# PowerManagementMysensors.net
KiCad netlist of a schematic drawn in EAGLE
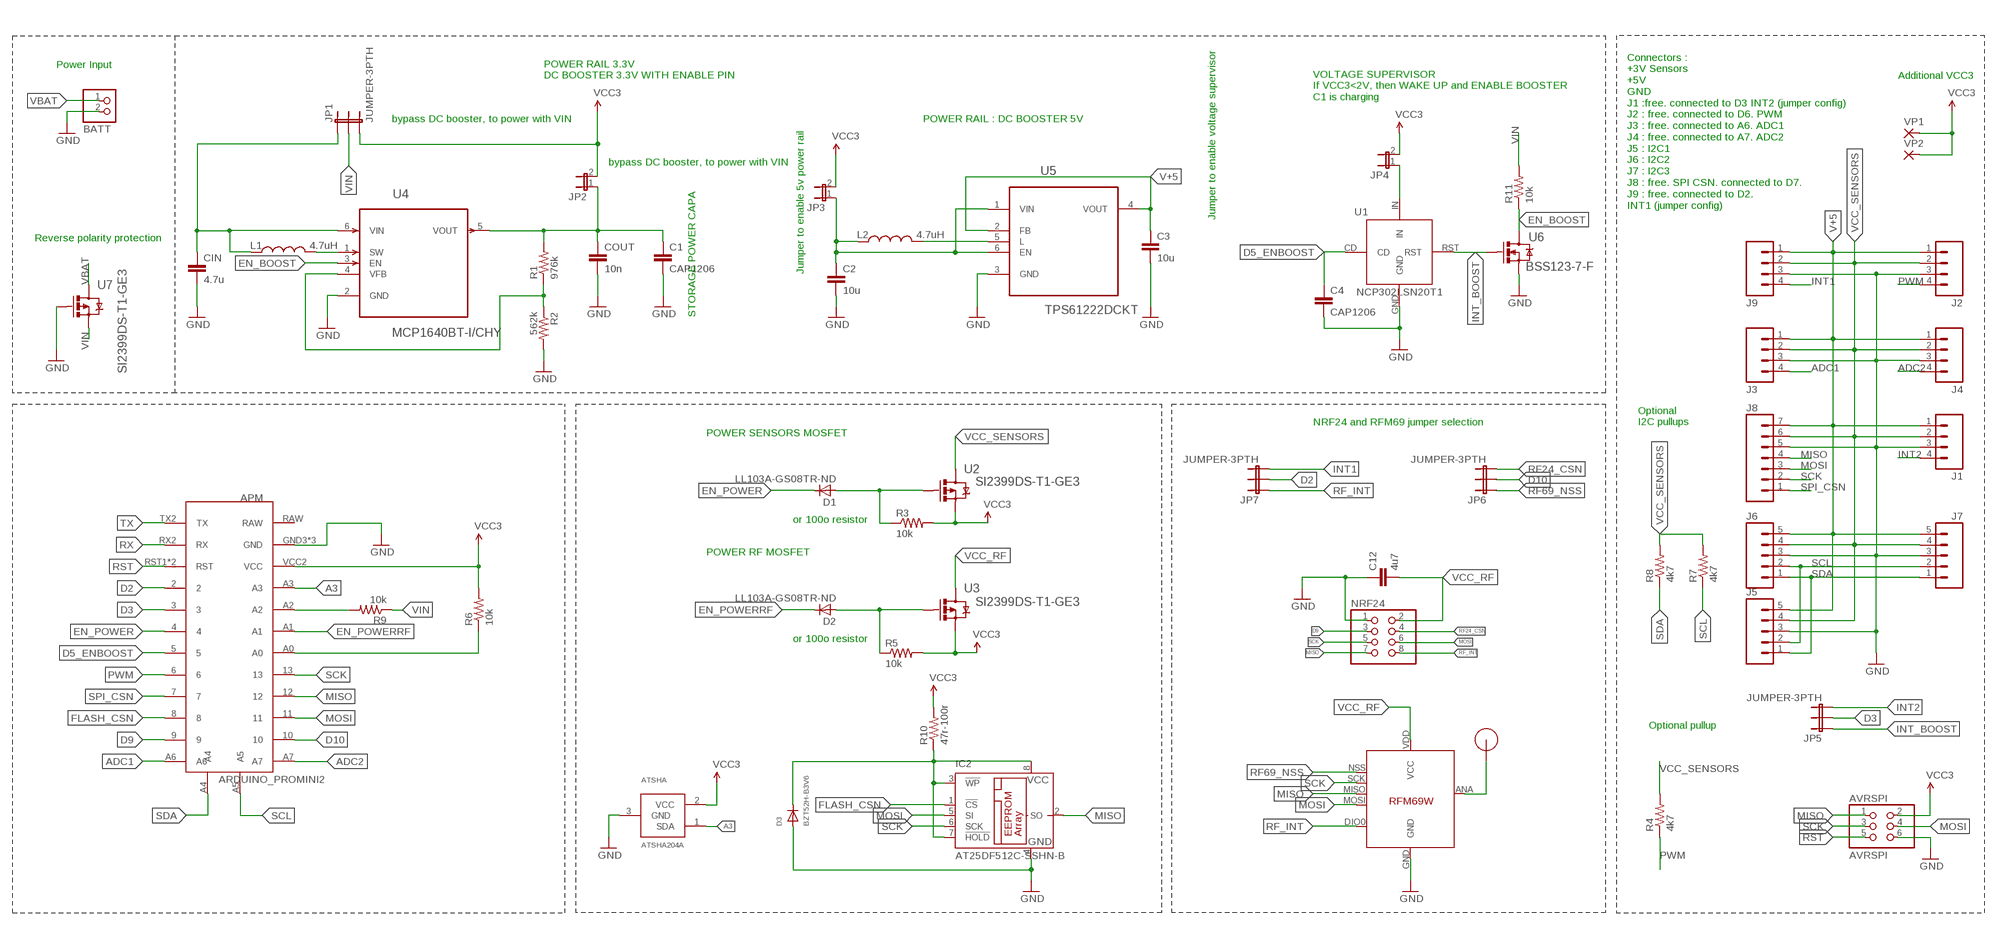
[diagram p0: schematic, sheet 1]

(export (version "E")
  (design (tool "Eeschema 10.0.6"))
  (components
    (comp (ref "ANT")
      (value "RFM12B_ANTENNA")
      (footprint "eagle-import:RFM12B-ANTENNA")
      (libsource (lib "eagle-import") (part "RFM12B_ANTENNA"))
    )
    (comp (ref "APM")
      (value "ARDUINO_PROMINI2")
      (footprint "eagle-import:ARDUINO_PROMINI2")
      (libsource (lib "eagle-import") (part "ARDUINO_PROMINI2"))
    )
    (comp (ref "ATSHA")
      (value "ATSHA204A")
      (footprint "eagle-import:SOT23")
      (libsource (lib "eagle-import") (part "ATSHA204A"))
    )
    (comp (ref "AVRSPI")
      (value "AVRSPI")
      (footprint "eagle-import:2X03")
      (libsource (lib "eagle-import") (part "PINHD-2X3"))
    )
    (comp (ref "BATT")
      (value "JST_2PIN-THM")
      (footprint "eagle-import:JST-PH-2-THM")
      (libsource (lib "eagle-import") (part "JST_2PIN-THM"))
    )
    (comp (ref "C1")
      (value "CAP1206")
      (footprint "eagle-import:CAP1206")
      (libsource (lib "eagle-import") (part "CAP1206"))
    )
    (comp (ref "C2")
      (value "10u")
      (footprint "eagle-import:CAP1206")
      (libsource (lib "eagle-import") (part "CAP1206"))
    )
    (comp (ref "C3")
      (value "10u")
      (footprint "eagle-import:CAP1206")
      (libsource (lib "eagle-import") (part "CAP1206"))
    )
    (comp (ref "C4")
      (value "CAP1206")
      (footprint "eagle-import:CAP1206")
      (libsource (lib "eagle-import") (part "CAP1206"))
    )
    (comp (ref "C12")
      (value "4u7")
      (footprint "eagle-import:CAP1206")
      (libsource (lib "eagle-import") (part "CAP1206"))
    )
    (comp (ref "CIN")
      (value "4.7u")
      (footprint "eagle-import:CAP1206")
      (libsource (lib "eagle-import") (part "CAP1206"))
    )
    (comp (ref "COUT")
      (value "10n")
      (footprint "eagle-import:CAP1206")
      (libsource (lib "eagle-import") (part "CAP1206"))
    )
    (comp (ref "D1")
      (value "LL103A-GS08TR-ND")
      (footprint "eagle-import:SOD80")
      (libsource (lib "eagle-import") (part "D-SOD-80"))
    )
    (comp (ref "D2")
      (value "LL103A-GS08TR-ND")
      (footprint "eagle-import:SOD80")
      (libsource (lib "eagle-import") (part "D-SOD-80"))
    )
    (comp (ref "D3")
      (value "BZT52H-B3V6")
      (footprint "eagle-import:SOD-123")
      (libsource (lib "eagle-import") (part "DIODESOD-123"))
    )
    (comp (ref "IC2")
      (value "AT25DF512C-SSHN-B")
      (footprint "eagle-import:SO-08")
      (fields (field (name "MF") "MICROCHIP") (field (name "MPN") "25AA080/SN"))
      (libsource (lib "eagle-import") (part "25SNAA080"))
    )
    (comp (ref "J1")
      (value "M041X04_NO_SILK")
      (footprint "eagle-import:1X04_NO_SILK")
      (libsource (lib "eagle-import") (part "M041X04_NO_SILK"))
    )
    (comp (ref "J2")
      (value "M041X04_NO_SILK")
      (footprint "eagle-import:1X04_NO_SILK")
      (libsource (lib "eagle-import") (part "M041X04_NO_SILK"))
    )
    (comp (ref "J3")
      (value "M041X04_NO_SILK")
      (footprint "eagle-import:1X04_NO_SILK")
      (libsource (lib "eagle-import") (part "M041X04_NO_SILK"))
    )
    (comp (ref "J4")
      (value "M041X04_NO_SILK")
      (footprint "eagle-import:1X04_NO_SILK")
      (libsource (lib "eagle-import") (part "M041X04_NO_SILK"))
    )
    (comp (ref "J5")
      (value "M05NO_SILK")
      (footprint "eagle-import:1X05_NO_SILK")
      (libsource (lib "eagle-import") (part "M05NO_SILK"))
    )
    (comp (ref "J6")
      (value "M05NO_SILK")
      (footprint "eagle-import:1X05_NO_SILK")
      (libsource (lib "eagle-import") (part "M05NO_SILK"))
    )
    (comp (ref "J7")
      (value "M05NO_SILK")
      (footprint "eagle-import:1X05_NO_SILK")
      (libsource (lib "eagle-import") (part "M05NO_SILK"))
    )
    (comp (ref "J8")
      (value "M07")
      (footprint "eagle-import:1X07")
      (libsource (lib "eagle-import") (part "M07"))
    )
    (comp (ref "J9")
      (value "M041X04_NO_SILK")
      (footprint "eagle-import:1X04_NO_SILK")
      (libsource (lib "eagle-import") (part "M041X04_NO_SILK"))
    )
    (comp (ref "JP1")
      (value "JUMPER-3PTH")
      (footprint "eagle-import:1X03")
      (libsource (lib "eagle-import") (part "JUMPER-3PTH"))
    )
    (comp (ref "JP2")
      (value "JUMPER-2PTH")
      (footprint "eagle-import:1X02")
      (libsource (lib "eagle-import") (part "JUMPER-2PTH"))
    )
    (comp (ref "JP3")
      (value "JUMPER-2PTH")
      (footprint "eagle-import:1X02")
      (libsource (lib "eagle-import") (part "JUMPER-2PTH"))
    )
    (comp (ref "JP4")
      (value "JUMPER-2PTH")
      (footprint "eagle-import:1X02")
      (libsource (lib "eagle-import") (part "JUMPER-2PTH"))
    )
    (comp (ref "JP5")
      (value "JUMPER-3PTH")
      (footprint "eagle-import:1X03")
      (libsource (lib "eagle-import") (part "JUMPER-3PTH"))
    )
    (comp (ref "JP6")
      (value "JUMPER-3PTH")
      (footprint "eagle-import:1X03")
      (libsource (lib "eagle-import") (part "JUMPER-3PTH"))
    )
    (comp (ref "JP7")
      (value "JUMPER-3PTH")
      (footprint "eagle-import:1X03")
      (libsource (lib "eagle-import") (part "JUMPER-3PTH"))
    )
    (comp (ref "L1")
      (value "4.7uH")
      (footprint "eagle-import:0805")
      (libsource (lib "eagle-import") (part "INDUCTOR0805"))
    )
    (comp (ref "L2")
      (value "4.7uH")
      (footprint "eagle-import:0805")
      (libsource (lib "eagle-import") (part "INDUCTOR0805"))
    )
    (comp (ref "NRF24")
      (value "PINHD-2X4")
      (footprint "eagle-import:2X04")
      (libsource (lib "eagle-import") (part "PINHD-2X4"))
    )
    (comp (ref "R1")
      (value "976k")
      (footprint "eagle-import:1206")
      (libsource (lib "eagle-import") (part "RESISTOR1206"))
    )
    (comp (ref "R2")
      (value "562k")
      (footprint "eagle-import:1206")
      (libsource (lib "eagle-import") (part "RESISTOR1206"))
    )
    (comp (ref "R3")
      (value "10k")
      (footprint "eagle-import:1206")
      (libsource (lib "eagle-import") (part "RESISTOR1206"))
    )
    (comp (ref "R4")
      (value "4k7")
      (footprint "eagle-import:1206")
      (libsource (lib "eagle-import") (part "RESISTOR1206"))
    )
    (comp (ref "R5")
      (value "10k")
      (footprint "eagle-import:1206")
      (libsource (lib "eagle-import") (part "RESISTOR1206"))
    )
    (comp (ref "R6")
      (value "10k")
      (footprint "eagle-import:1206")
      (libsource (lib "eagle-import") (part "RESISTOR1206"))
    )
    (comp (ref "R7")
      (value "4k7")
      (footprint "eagle-import:1206")
      (libsource (lib "eagle-import") (part "RESISTOR1206"))
    )
    (comp (ref "R8")
      (value "4k7")
      (footprint "eagle-import:1206")
      (libsource (lib "eagle-import") (part "RESISTOR1206"))
    )
    (comp (ref "R9")
      (value "10k")
      (footprint "eagle-import:1206")
      (libsource (lib "eagle-import") (part "RESISTOR1206"))
    )
    (comp (ref "R10")
      (value "47r-100r")
      (footprint "eagle-import:1206")
      (libsource (lib "eagle-import") (part "RESISTOR1206"))
    )
    (comp (ref "R11")
      (value "10k")
      (footprint "eagle-import:1206")
      (libsource (lib "eagle-import") (part "RESISTOR1206"))
    )
    (comp (ref "RFM69")
      (value "RFM69")
      (footprint "eagle-import:RFM69W-MINPADS")
      (libsource (lib "eagle-import") (part "RFM69"))
    )
    (comp (ref "U1")
      (value "NCP302LSN20T1")
      (footprint "eagle-import:NCP302LSN20T1")
      (libsource (lib "eagle-import") (part "NCP302LSN20T1"))
    )
    (comp (ref "U2")
      (value "SI2399DS-T1-GE3")
      (footprint "eagle-import:SOT95P237X112-3N")
      (libsource (lib "eagle-import") (part "SI2399DS-T1-GE3"))
    )
    (comp (ref "U3")
      (value "SI2399DS-T1-GE3")
      (footprint "eagle-import:SOT95P237X112-3N")
      (libsource (lib "eagle-import") (part "SI2399DS-T1-GE3"))
    )
    (comp (ref "U4")
      (value "MCP1640BT-I/CHY")
      (footprint "eagle-import:SOT95P270X145-6N")
      (libsource (lib "eagle-import") (part "MCP1640BT-I/CHY"))
    )
    (comp (ref "U5")
      (value "TPS61222DCKT")
      (footprint "eagle-import:SOT65P210X110-6N")
      (libsource (lib "eagle-import") (part "TPS61222DCKT"))
    )
    (comp (ref "U6")
      (value "BSS123-7-F")
      (footprint "eagle-import:SOT95P240X110-3N")
      (libsource (lib "eagle-import") (part "BSS123-7-F"))
    )
    (comp (ref "U7")
      (value "SI2399DS-T1-GE3")
      (footprint "eagle-import:SOT95P237X112-3N")
      (libsource (lib "eagle-import") (part "SI2399DS-T1-GE3"))
    )
    (comp (ref "VP1")
      (value "1,6/0,9")
      (footprint "eagle-import:1,6_0,9")
      (libsource (lib "eagle-import") (part "1,6/0,9"))
    )
    (comp (ref "VP2")
      (value "1,6/0,9")
      (footprint "eagle-import:1,6_0,9")
      (libsource (lib "eagle-import") (part "1,6/0,9"))
    )
  )
  (nets
    (net (code "1") (name "A3") (class "Default")
      (node (ref "APM") (pin "A3") (pinfunction "A3_A3") (pintype "bidirectional"))
      (node (ref "ATSHA") (pin "1") (pinfunction "SDA_1") (pintype "bidirectional"))
    )
    (net (code "2") (name "ADC1") (class "Default")
      (node (ref "APM") (pin "A6") (pinfunction "A6_A6") (pintype "bidirectional"))
      (node (ref "J3") (pin "4") (pinfunction "4_4") (pintype "passive"))
    )
    (net (code "3") (name "ADC2") (class "Default")
      (node (ref "APM") (pin "A7") (pinfunction "A7_A7") (pintype "bidirectional"))
      (node (ref "J4") (pin "4") (pinfunction "4_4") (pintype "passive"))
    )
    (net (code "4") (name "D2") (class "Default")
      (node (ref "APM") (pin "2") (pinfunction "2_2") (pintype "bidirectional"))
      (node (ref "JP7") (pin "2") (pinfunction "2_2") (pintype "passive"))
    )
    (net (code "5") (name "D3") (class "Default")
      (node (ref "APM") (pin "3") (pinfunction "3_3") (pintype "bidirectional"))
      (node (ref "JP5") (pin "2") (pinfunction "2_2") (pintype "passive"))
    )
    (net (code "6") (name "D5_ENBOOST") (class "Default")
      (node (ref "APM") (pin "5") (pinfunction "5_5") (pintype "bidirectional"))
      (node (ref "C4") (pin "1") (pinfunction "1_1") (pintype "passive"))
      (node (ref "U1") (pin "CD") (pinfunction "CD_CD") (pintype "bidirectional"))
    )
    (net (code "7") (name "D9") (class "Default")
      (node (ref "APM") (pin "9") (pinfunction "9_9") (pintype "bidirectional"))
      (node (ref "NRF24") (pin "3") (pinfunction "3_3") (pintype "passive"))
    )
    (net (code "8") (name "D10") (class "Default")
      (node (ref "APM") (pin "10") (pinfunction "10_10") (pintype "bidirectional"))
      (node (ref "JP6") (pin "2") (pinfunction "2_2") (pintype "passive"))
    )
    (net (code "9") (name "EN_BOOST") (class "Default")
      (node (ref "R11") (pin "1") (pinfunction "1_1") (pintype "passive"))
      (node (ref "U4") (pin "3") (pinfunction "EN_3") (pintype "input"))
      (node (ref "U6") (pin "3") (pinfunction "D_3") (pintype "passive"))
    )
    (net (code "10") (name "EN_POWER") (class "Default")
      (node (ref "APM") (pin "4") (pinfunction "4_4") (pintype "bidirectional"))
      (node (ref "D1") (pin "1") (pinfunction "C_1") (pintype "passive"))
    )
    (net (code "11") (name "EN_POWERRF") (class "Default")
      (node (ref "APM") (pin "A1") (pinfunction "A1_A1") (pintype "bidirectional"))
      (node (ref "D2") (pin "1") (pinfunction "C_1") (pintype "passive"))
    )
    (net (code "12") (name "FLASH_CSN") (class "Default")
      (node (ref "APM") (pin "8") (pinfunction "8_8") (pintype "bidirectional"))
      (node (ref "IC2") (pin "1") (pinfunction "~{CS}_1") (pintype "input"))
    )
    (net (code "13") (name "GND") (class "Default")
      (node (ref "APM") (pin "GND3") (pinfunction "GND_GND3") (pintype "bidirectional"))
      (node (ref "APM") (pin "GND4") (pinfunction "GND_GND4") (pintype "bidirectional"))
      (node (ref "APM") (pin "GND5") (pinfunction "GND_GND5") (pintype "bidirectional"))
      (node (ref "ATSHA") (pin "3") (pinfunction "GND_3") (pintype "bidirectional"))
      (node (ref "AVRSPI") (pin "6") (pinfunction "6_6") (pintype "passive"))
      (node (ref "BATT") (pin "2") (pinfunction "1_2") (pintype "passive"))
      (node (ref "C1") (pin "2") (pinfunction "2_2") (pintype "passive"))
      (node (ref "C12") (pin "1") (pinfunction "1_1") (pintype "passive"))
      (node (ref "C2") (pin "2") (pinfunction "2_2") (pintype "passive"))
      (node (ref "C3") (pin "2") (pinfunction "2_2") (pintype "passive"))
      (node (ref "C4") (pin "2") (pinfunction "2_2") (pintype "passive"))
      (node (ref "CIN") (pin "2") (pinfunction "2_2") (pintype "passive"))
      (node (ref "COUT") (pin "2") (pinfunction "2_2") (pintype "passive"))
      (node (ref "D3") (pin "A") (pinfunction "A_A") (pintype "passive"))
      (node (ref "IC2") (pin "4") (pinfunction "GND_4") (pintype "power_in"))
      (node (ref "J1") (pin "3") (pinfunction "3_3") (pintype "passive"))
      (node (ref "J2") (pin "3") (pinfunction "3_3") (pintype "passive"))
      (node (ref "J3") (pin "3") (pinfunction "3_3") (pintype "passive"))
      (node (ref "J4") (pin "3") (pinfunction "3_3") (pintype "passive"))
      (node (ref "J5") (pin "3") (pinfunction "3_3") (pintype "passive"))
      (node (ref "J6") (pin "3") (pinfunction "3_3") (pintype "passive"))
      (node (ref "J7") (pin "3") (pinfunction "3_3") (pintype "passive"))
      (node (ref "J8") (pin "5") (pinfunction "5_5") (pintype "passive"))
      (node (ref "J9") (pin "3") (pinfunction "3_3") (pintype "passive"))
      (node (ref "NRF24") (pin "1") (pinfunction "1_1") (pintype "passive"))
      (node (ref "R2") (pin "2") (pinfunction "2_2") (pintype "passive"))
      (node (ref "RFM69") (pin "GND") (pinfunction "GND_GND") (pintype "power_in"))
      (node (ref "U1") (pin "GND") (pinfunction "GND_GND") (pintype "bidirectional"))
      (node (ref "U4") (pin "2") (pinfunction "GND_2") (pintype "passive"))
      (node (ref "U5") (pin "3") (pinfunction "GND_3") (pintype "passive"))
      (node (ref "U6") (pin "2") (pinfunction "S_2") (pintype "passive"))
      (node (ref "U7") (pin "1") (pinfunction "G_1") (pintype "passive"))
    )
    (net (code "14") (name "INT1") (class "Default")
      (node (ref "J9") (pin "4") (pinfunction "4_4") (pintype "passive"))
      (node (ref "JP7") (pin "3") (pinfunction "3_3") (pintype "passive"))
    )
    (net (code "15") (name "INT2") (class "Default")
      (node (ref "J1") (pin "4") (pinfunction "4_4") (pintype "passive"))
      (node (ref "JP5") (pin "3") (pinfunction "3_3") (pintype "passive"))
    )
    (net (code "16") (name "INT_BOOST") (class "Default")
      (node (ref "JP5") (pin "1") (pinfunction "1_1") (pintype "passive"))
      (node (ref "U1") (pin "RST") (pinfunction "RST_RST") (pintype "bidirectional"))
      (node (ref "U6") (pin "1") (pinfunction "G_1") (pintype "passive"))
    )
    (net (code "17") (name "MISO") (class "Default")
      (node (ref "APM") (pin "12") (pinfunction "12_12") (pintype "bidirectional"))
      (node (ref "AVRSPI") (pin "1") (pinfunction "1_1") (pintype "passive"))
      (node (ref "IC2") (pin "2") (pinfunction "SO_2") (pintype "bidirectional"))
      (node (ref "J8") (pin "4") (pinfunction "4_4") (pintype "passive"))
      (node (ref "NRF24") (pin "7") (pinfunction "7_7") (pintype "passive"))
      (node (ref "RFM69") (pin "MISO") (pinfunction "MISO_MISO") (pintype "input"))
    )
    (net (code "18") (name "MOSI") (class "Default")
      (node (ref "APM") (pin "11") (pinfunction "11_11") (pintype "bidirectional"))
      (node (ref "AVRSPI") (pin "4") (pinfunction "4_4") (pintype "passive"))
      (node (ref "IC2") (pin "5") (pinfunction "SI_5") (pintype "input"))
      (node (ref "J8") (pin "3") (pinfunction "3_3") (pintype "passive"))
      (node (ref "NRF24") (pin "6") (pinfunction "6_6") (pintype "passive"))
      (node (ref "RFM69") (pin "MOSI") (pinfunction "MOSI_MOSI") (pintype "output"))
    )
    (net (code "19") (name "Net-(ANT-1)") (class "Default")
      (node (ref "ANT") (pin "P$1") (pinfunction "1_P$1") (pintype "bidirectional"))
      (node (ref "RFM69") (pin "ANA") (pinfunction "ANT_ANA") (pintype "passive"))
    )
    (net (code "20") (name "Net-(APM-PadA0)") (class "Default")
      (node (ref "APM") (pin "A0") (pinfunction "A0_A0") (pintype "bidirectional"))
      (node (ref "R6") (pin "1") (pinfunction "1_1") (pintype "passive"))
    )
    (net (code "21") (name "Net-(APM-PadA2)") (class "Default")
      (node (ref "APM") (pin "A2") (pinfunction "A2_A2") (pintype "bidirectional"))
      (node (ref "R9") (pin "2") (pinfunction "2_2") (pintype "passive"))
    )
    (net (code "22") (name "Net-(D1-A)") (class "Default")
      (node (ref "D1") (pin "2") (pinfunction "A_2") (pintype "passive"))
      (node (ref "R3") (pin "1") (pinfunction "1_1") (pintype "passive"))
      (node (ref "U2") (pin "1") (pinfunction "G_1") (pintype "passive"))
    )
    (net (code "23") (name "Net-(D2-A)") (class "Default")
      (node (ref "D2") (pin "2") (pinfunction "A_2") (pintype "passive"))
      (node (ref "R5") (pin "1") (pinfunction "1_1") (pintype "passive"))
      (node (ref "U3") (pin "1") (pinfunction "G_1") (pintype "passive"))
    )
    (net (code "24") (name "Net-(IC2-VCC)") (class "Default")
      (node (ref "D3") (pin "C") (pinfunction "C_C") (pintype "passive"))
      (node (ref "IC2") (pin "3") (pinfunction "~{WP}_3") (pintype "input"))
      (node (ref "IC2") (pin "7") (pinfunction "~{HOLD}_7") (pintype "input"))
      (node (ref "IC2") (pin "8") (pinfunction "VCC_8") (pintype "power_in"))
      (node (ref "R10") (pin "1") (pinfunction "1_1") (pintype "passive"))
    )
    (net (code "25") (name "Net-(JP4-Pad1)") (class "Default")
      (node (ref "JP4") (pin "1") (pinfunction "1_1") (pintype "passive"))
      (node (ref "U1") (pin "IN") (pinfunction "IN_IN") (pintype "bidirectional"))
    )
    (net (code "26") (name "Net-(U4-SW)") (class "Default")
      (node (ref "L1") (pin "2") (pinfunction "2_2") (pintype "passive"))
      (node (ref "U4") (pin "1") (pinfunction "SW_1") (pintype "input"))
    )
    (net (code "27") (name "Net-(U4-VFB)") (class "Default")
      (node (ref "R1") (pin "1") (pinfunction "1_1") (pintype "passive"))
      (node (ref "R2") (pin "1") (pinfunction "1_1") (pintype "passive"))
      (node (ref "U4") (pin "4") (pinfunction "VFB_4") (pintype "input"))
    )
    (net (code "28") (name "Net-(U4-VIN)") (class "Default")
      (node (ref "CIN") (pin "1") (pinfunction "1_1") (pintype "passive"))
      (node (ref "JP1") (pin "1") (pinfunction "1_1") (pintype "passive"))
      (node (ref "L1") (pin "1") (pinfunction "1_1") (pintype "passive"))
      (node (ref "U4") (pin "6") (pinfunction "VIN_6") (pintype "input"))
    )
    (net (code "29") (name "Net-(U4-VOUT)") (class "Default")
      (node (ref "C1") (pin "1") (pinfunction "1_1") (pintype "passive"))
      (node (ref "COUT") (pin "1") (pinfunction "1_1") (pintype "passive"))
      (node (ref "JP2") (pin "1") (pinfunction "1_1") (pintype "passive"))
      (node (ref "R1") (pin "2") (pinfunction "2_2") (pintype "passive"))
      (node (ref "U4") (pin "5") (pinfunction "VOUT_5") (pintype "output"))
    )
    (net (code "30") (name "Net-(U5-EN)") (class "Default")
      (node (ref "C2") (pin "1") (pinfunction "1_1") (pintype "passive"))
      (node (ref "JP3") (pin "1") (pinfunction "1_1") (pintype "passive"))
      (node (ref "L2") (pin "1") (pinfunction "1_1") (pintype "passive"))
      (node (ref "U5") (pin "1") (pinfunction "VIN_1") (pintype "input"))
      (node (ref "U5") (pin "6") (pinfunction "EN_6") (pintype "input"))
    )
    (net (code "31") (name "Net-(U5-L)") (class "Default")
      (node (ref "L2") (pin "2") (pinfunction "2_2") (pintype "passive"))
      (node (ref "U5") (pin "5") (pinfunction "L_5") (pintype "passive"))
    )
    (net (code "32") (name "PWM") (class "Default")
      (node (ref "APM") (pin "6") (pinfunction "6_6") (pintype "bidirectional"))
      (node (ref "J2") (pin "4") (pinfunction "4_4") (pintype "passive"))
      (node (ref "R4") (pin "1") (pinfunction "1_1") (pintype "passive"))
    )
    (net (code "33") (name "RF24_CSN") (class "Default")
      (node (ref "JP6") (pin "3") (pinfunction "3_3") (pintype "passive"))
      (node (ref "NRF24") (pin "4") (pinfunction "4_4") (pintype "passive"))
    )
    (net (code "34") (name "RF69_NSS") (class "Default")
      (node (ref "JP6") (pin "1") (pinfunction "1_1") (pintype "passive"))
      (node (ref "RFM69") (pin "NSS") (pinfunction "SEL_NSS") (pintype "input"))
    )
    (net (code "35") (name "RF_INT") (class "Default")
      (node (ref "JP7") (pin "1") (pinfunction "1_1") (pintype "passive"))
      (node (ref "NRF24") (pin "8") (pinfunction "8_8") (pintype "passive"))
      (node (ref "RFM69") (pin "DIO0") (pinfunction "DIO0_DIO0") (pintype "open_collector"))
    )
    (net (code "36") (name "RST") (class "Default")
      (node (ref "APM") (pin "RST1") (pinfunction "RST_RST1") (pintype "bidirectional"))
      (node (ref "APM") (pin "RST2") (pinfunction "RST_RST2") (pintype "bidirectional"))
      (node (ref "AVRSPI") (pin "5") (pinfunction "5_5") (pintype "passive"))
    )
    (net (code "37") (name "RX") (class "Default")
      (node (ref "APM") (pin "RX2") (pinfunction "RX_RX2") (pintype "bidirectional"))
    )
    (net (code "38") (name "SCK") (class "Default")
      (node (ref "APM") (pin "13") (pinfunction "13_13") (pintype "bidirectional"))
      (node (ref "AVRSPI") (pin "3") (pinfunction "3_3") (pintype "passive"))
      (node (ref "IC2") (pin "6") (pinfunction "SCK_6") (pintype "input"))
      (node (ref "J8") (pin "2") (pinfunction "2_2") (pintype "passive"))
      (node (ref "NRF24") (pin "5") (pinfunction "5_5") (pintype "passive"))
      (node (ref "RFM69") (pin "SCK") (pinfunction "SCK_SCK") (pintype "input"))
    )
    (net (code "39") (name "SCL") (class "Default")
      (node (ref "APM") (pin "A5") (pinfunction "A5_A5") (pintype "bidirectional"))
      (node (ref "J5") (pin "2") (pinfunction "2_2") (pintype "passive"))
      (node (ref "J6") (pin "2") (pinfunction "2_2") (pintype "passive"))
      (node (ref "J7") (pin "2") (pinfunction "2_2") (pintype "passive"))
      (node (ref "R7") (pin "1") (pinfunction "1_1") (pintype "passive"))
    )
    (net (code "40") (name "SDA") (class "Default")
      (node (ref "APM") (pin "A4") (pinfunction "A4_A4") (pintype "bidirectional"))
      (node (ref "J5") (pin "1") (pinfunction "1_1") (pintype "passive"))
      (node (ref "J6") (pin "1") (pinfunction "1_1") (pintype "passive"))
      (node (ref "J7") (pin "1") (pinfunction "1_1") (pintype "passive"))
      (node (ref "R8") (pin "1") (pinfunction "1_1") (pintype "passive"))
    )
    (net (code "41") (name "SPI_CSN") (class "Default")
      (node (ref "APM") (pin "7") (pinfunction "7_7") (pintype "bidirectional"))
      (node (ref "J8") (pin "1") (pinfunction "1_1") (pintype "passive"))
    )
    (net (code "42") (name "TX") (class "Default")
      (node (ref "APM") (pin "TX2") (pinfunction "TX_TX2") (pintype "bidirectional"))
    )
    (net (code "43") (name "V+5") (class "Default")
      (node (ref "C3") (pin "1") (pinfunction "1_1") (pintype "passive"))
      (node (ref "J1") (pin "1") (pinfunction "1_1") (pintype "passive"))
      (node (ref "J2") (pin "1") (pinfunction "1_1") (pintype "passive"))
      (node (ref "J3") (pin "1") (pinfunction "1_1") (pintype "passive"))
      (node (ref "J4") (pin "1") (pinfunction "1_1") (pintype "passive"))
      (node (ref "J5") (pin "5") (pinfunction "5_5") (pintype "passive"))
      (node (ref "J6") (pin "5") (pinfunction "5_5") (pintype "passive"))
      (node (ref "J7") (pin "5") (pinfunction "5_5") (pintype "passive"))
      (node (ref "J8") (pin "7") (pinfunction "7_7") (pintype "passive"))
      (node (ref "J9") (pin "1") (pinfunction "1_1") (pintype "passive"))
      (node (ref "U5") (pin "2") (pinfunction "FB_2") (pintype "input"))
      (node (ref "U5") (pin "4") (pinfunction "VOUT_4") (pintype "output"))
    )
    (net (code "44") (name "VBAT") (class "Default")
      (node (ref "BATT") (pin "1") (pinfunction "2_1") (pintype "passive"))
      (node (ref "U7") (pin "3") (pinfunction "D_3") (pintype "passive"))
    )
    (net (code "45") (name "VCC3") (class "Default")
      (node (ref "APM") (pin "VCC2") (pinfunction "VCC_VCC2") (pintype "bidirectional"))
      (node (ref "ATSHA") (pin "2") (pinfunction "VCC_2") (pintype "bidirectional"))
      (node (ref "AVRSPI") (pin "2") (pinfunction "2_2") (pintype "passive"))
      (node (ref "JP1") (pin "3") (pinfunction "3_3") (pintype "passive"))
      (node (ref "JP2") (pin "2") (pinfunction "2_2") (pintype "passive"))
      (node (ref "JP3") (pin "2") (pinfunction "2_2") (pintype "passive"))
      (node (ref "JP4") (pin "2") (pinfunction "2_2") (pintype "passive"))
      (node (ref "R10") (pin "2") (pinfunction "2_2") (pintype "passive"))
      (node (ref "R3") (pin "2") (pinfunction "2_2") (pintype "passive"))
      (node (ref "R5") (pin "2") (pinfunction "2_2") (pintype "passive"))
      (node (ref "R6") (pin "2") (pinfunction "2_2") (pintype "passive"))
      (node (ref "U2") (pin "2") (pinfunction "S_2") (pintype "passive"))
      (node (ref "U3") (pin "2") (pinfunction "S_2") (pintype "passive"))
      (node (ref "VP1") (pin "1") (pinfunction "P_1") (pintype "passive"))
      (node (ref "VP2") (pin "1") (pinfunction "P_1") (pintype "passive"))
    )
    (net (code "46") (name "VCC_RF") (class "Default")
      (node (ref "C12") (pin "2") (pinfunction "2_2") (pintype "passive"))
      (node (ref "NRF24") (pin "2") (pinfunction "2_2") (pintype "passive"))
      (node (ref "RFM69") (pin "VDD") (pinfunction "VCC_VDD") (pintype "power_in"))
      (node (ref "U3") (pin "3") (pinfunction "D_3") (pintype "passive"))
    )
    (net (code "47") (name "VCC_SENSORS") (class "Default")
      (node (ref "J1") (pin "2") (pinfunction "2_2") (pintype "passive"))
      (node (ref "J2") (pin "2") (pinfunction "2_2") (pintype "passive"))
      (node (ref "J3") (pin "2") (pinfunction "2_2") (pintype "passive"))
      (node (ref "J4") (pin "2") (pinfunction "2_2") (pintype "passive"))
      (node (ref "J5") (pin "4") (pinfunction "4_4") (pintype "passive"))
      (node (ref "J6") (pin "4") (pinfunction "4_4") (pintype "passive"))
      (node (ref "J7") (pin "4") (pinfunction "4_4") (pintype "passive"))
      (node (ref "J8") (pin "6") (pinfunction "6_6") (pintype "passive"))
      (node (ref "J9") (pin "2") (pinfunction "2_2") (pintype "passive"))
      (node (ref "R4") (pin "2") (pinfunction "2_2") (pintype "passive"))
      (node (ref "R7") (pin "2") (pinfunction "2_2") (pintype "passive"))
      (node (ref "R8") (pin "2") (pinfunction "2_2") (pintype "passive"))
      (node (ref "U2") (pin "3") (pinfunction "D_3") (pintype "passive"))
    )
    (net (code "48") (name "VIN") (class "Default")
      (node (ref "JP1") (pin "2") (pinfunction "2_2") (pintype "passive"))
      (node (ref "R11") (pin "2") (pinfunction "2_2") (pintype "passive"))
      (node (ref "R9") (pin "1") (pinfunction "1_1") (pintype "passive"))
      (node (ref "U7") (pin "2") (pinfunction "S_2") (pintype "passive"))
    )
    (net (code "49") (name "unconnected-(APM-PadRAW)") (class "Default")
      (node (ref "APM") (pin "RAW") (pinfunction "RAW_RAW") (pintype "bidirectional"))
    )
  )
)
